# adc-ldo.net
KiCad netlist of a schematic drawn in Altium Designer
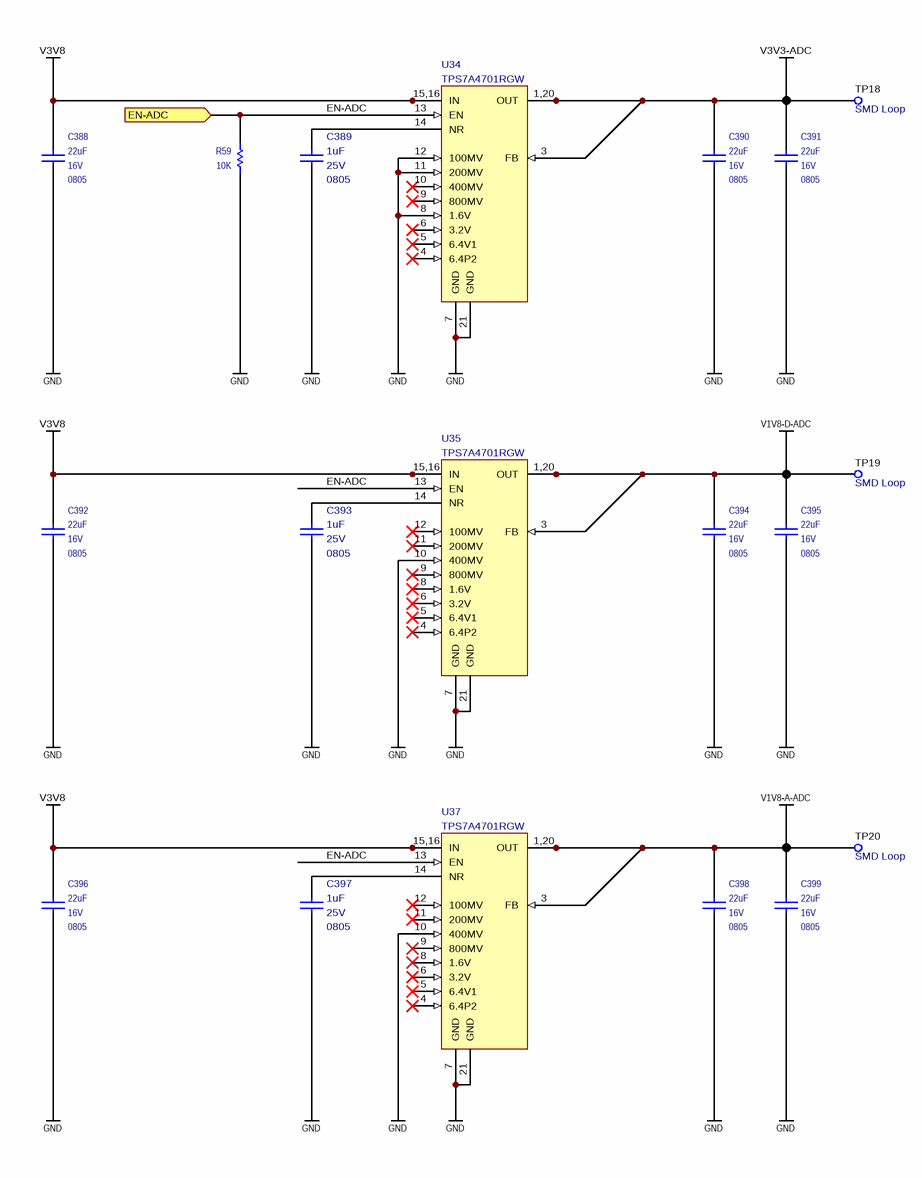
[diagram p0: adc-ldo.SchDoc]

(export (version "E")
  (design (tool "Eeschema 10.0.6"))
  (components
    (comp (ref "C388")
      (value "22uF")
      (footprint "generic:CAPC200X125X145L45N")
      (description "Ceramic Capacitor 22uF ±10% 16V X5R 0805")
      (fields
        (field (name "MANUFACTURER") "Samsung")
        (field (name "VOLTAGE") "16V")
        (field (name "PACKAGE") "0805")
        (field (name "TOLERANCE") "±10%")
      )
      (libsource (lib "generic") (part "CAP 0603"))
    )
    (comp (ref "C389")
      (value "1uF")
      (footprint "CAPC200X125X145L45N")
      (description "Ceramic Capacitor 1uF ±10% 25V X7R 0805")
      (fields
        (field (name "MANUFACTURER") "Taiyo Yuden")
        (field (name "TOLERANCE") "±10%")
        (field (name "PACKAGE") "0805")
        (field (name "VOLTAGE") "25V")
      )
      (libsource (lib "capacitors") (part "CAP"))
    )
    (comp (ref "C390")
      (value "22uF")
      (footprint "generic:CAPC200X125X145L45N")
      (description "Ceramic Capacitor 22uF ±10% 16V X5R 0805")
      (fields
        (field (name "MANUFACTURER") "Samsung")
        (field (name "VOLTAGE") "16V")
        (field (name "PACKAGE") "0805")
        (field (name "TOLERANCE") "±10%")
      )
      (libsource (lib "generic") (part "CAP 0603"))
    )
    (comp (ref "C391")
      (value "22uF")
      (footprint "generic:CAPC200X125X145L45N")
      (description "Ceramic Capacitor 22uF ±10% 16V X5R 0805")
      (fields
        (field (name "MANUFACTURER") "Samsung")
        (field (name "VOLTAGE") "16V")
        (field (name "PACKAGE") "0805")
        (field (name "TOLERANCE") "±10%")
      )
      (libsource (lib "generic") (part "CAP 0603"))
    )
    (comp (ref "C392")
      (value "22uF")
      (footprint "generic:CAPC200X125X145L45N")
      (description "Ceramic Capacitor 22uF ±10% 16V X5R 0805")
      (fields
        (field (name "MANUFACTURER") "Samsung")
        (field (name "VOLTAGE") "16V")
        (field (name "PACKAGE") "0805")
        (field (name "TOLERANCE") "±10%")
      )
      (libsource (lib "generic") (part "CAP 0603"))
    )
    (comp (ref "C393")
      (value "1uF")
      (footprint "CAPC200X125X145L45N")
      (description "Ceramic Capacitor 1uF ±10% 25V X7R 0805")
      (fields
        (field (name "MANUFACTURER") "Taiyo Yuden")
        (field (name "TOLERANCE") "±10%")
        (field (name "PACKAGE") "0805")
        (field (name "VOLTAGE") "25V")
      )
      (libsource (lib "capacitors") (part "CAP"))
    )
    (comp (ref "C394")
      (value "22uF")
      (footprint "generic:CAPC200X125X145L45N")
      (description "Ceramic Capacitor 22uF ±10% 16V X5R 0805")
      (fields
        (field (name "MANUFACTURER") "Samsung")
        (field (name "VOLTAGE") "16V")
        (field (name "PACKAGE") "0805")
        (field (name "TOLERANCE") "±10%")
      )
      (libsource (lib "generic") (part "CAP 0603"))
    )
    (comp (ref "C395")
      (value "22uF")
      (footprint "generic:CAPC200X125X145L45N")
      (description "Ceramic Capacitor 22uF ±10% 16V X5R 0805")
      (fields
        (field (name "MANUFACTURER") "Samsung")
        (field (name "VOLTAGE") "16V")
        (field (name "PACKAGE") "0805")
        (field (name "TOLERANCE") "±10%")
      )
      (libsource (lib "generic") (part "CAP 0603"))
    )
    (comp (ref "C396")
      (value "22uF")
      (footprint "generic:CAPC200X125X145L45N")
      (description "Ceramic Capacitor 22uF ±10% 16V X5R 0805")
      (fields
        (field (name "MANUFACTURER") "Samsung")
        (field (name "VOLTAGE") "16V")
        (field (name "PACKAGE") "0805")
        (field (name "TOLERANCE") "±10%")
      )
      (libsource (lib "generic") (part "CAP 0603"))
    )
    (comp (ref "C397")
      (value "1uF")
      (footprint "CAPC200X125X145L45N")
      (description "Ceramic Capacitor 1uF ±10% 25V X7R 0805")
      (fields
        (field (name "MANUFACTURER") "Taiyo Yuden")
        (field (name "TOLERANCE") "±10%")
        (field (name "PACKAGE") "0805")
        (field (name "VOLTAGE") "25V")
      )
      (libsource (lib "capacitors") (part "CAP"))
    )
    (comp (ref "C398")
      (value "22uF")
      (footprint "generic:CAPC200X125X145L45N")
      (description "Ceramic Capacitor 22uF ±10% 16V X5R 0805")
      (fields
        (field (name "MANUFACTURER") "Samsung")
        (field (name "VOLTAGE") "16V")
        (field (name "PACKAGE") "0805")
        (field (name "TOLERANCE") "±10%")
      )
      (libsource (lib "generic") (part "CAP 0603"))
    )
    (comp (ref "C399")
      (value "22uF")
      (footprint "generic:CAPC200X125X145L45N")
      (description "Ceramic Capacitor 22uF ±10% 16V X5R 0805")
      (fields
        (field (name "MANUFACTURER") "Samsung")
        (field (name "VOLTAGE") "16V")
        (field (name "PACKAGE") "0805")
        (field (name "TOLERANCE") "±10%")
      )
      (libsource (lib "generic") (part "CAP 0603"))
    )
    (comp (ref "R59")
      (value "10K")
      (footprint "RESC1005X40N")
      (description "Thick Film Resistor 10k ±1% 0.1W 50V 0402")
      (fields (field (name "MANUFACTURER") "Panasonic") (field (name "TOLERANCE") "±1%"))
      (libsource (lib "Graviton") (part "RES 0402"))
    )
    (comp (ref "TP18")
      (value "5015")
      (footprint "keystone:5015")
      (description "Test Point SMD")
      (fields (field (name "MANUFACTURER") "Keystone") (field (name "NOTES") "SMD Loop"))
      (libsource (lib "generic") (part "TEST_POINT_SMD_50"))
    )
    (comp (ref "TP19")
      (value "5015")
      (footprint "keystone:5015")
      (description "Test Point SMD")
      (fields (field (name "MANUFACTURER") "Keystone") (field (name "NOTES") "SMD Loop"))
      (libsource (lib "generic") (part "TEST_POINT_SMD_50"))
    )
    (comp (ref "TP20")
      (value "5015")
      (footprint "keystone:5015")
      (description "Test Point SMD")
      (fields (field (name "MANUFACTURER") "Keystone") (field (name "NOTES") "SMD Loop"))
      (libsource (lib "generic") (part "TEST_POINT_SMD_50"))
    )
    (comp (ref "U34")
      (value "TPS7A4701RGW")
      (footprint "QFN65P500X500X100-21N")
      (description "Low-Dropout Linear Regulator 20-VQFN")
      (fields (field (name "MANUFACTURER") "Texas Instruments"))
      (libsource (lib "ti") (part "TPS7A4701RGW_1"))
    )
    (comp (ref "U35")
      (value "TPS7A4701RGW")
      (footprint "QFN65P500X500X100-21N")
      (description "Low-Dropout Linear Regulator 20-VQFN")
      (fields (field (name "MANUFACTURER") "Texas Instruments"))
      (libsource (lib "ti") (part "TPS7A4701RGW_1"))
    )
    (comp (ref "U37")
      (value "TPS7A4701RGW")
      (footprint "QFN65P500X500X100-21N")
      (description "Low-Dropout Linear Regulator 20-VQFN")
      (fields (field (name "MANUFACTURER") "Texas Instruments"))
      (libsource (lib "ti") (part "TPS7A4701RGW_1"))
    )
  )
  (nets
    (net (code "1") (name "/EN-ADC") (class "Default")
      (node (ref "R59") (pin "1") (pinfunction "1_1") (pintype "passive"))
      (node (ref "U34") (pin "13") (pinfunction "EN_13") (pintype "input"))
      (node (ref "U35") (pin "13") (pinfunction "EN_13") (pintype "input"))
      (node (ref "U37") (pin "13") (pinfunction "EN_13") (pintype "input"))
    )
    (net (code "2") (name "GND") (class "Default")
      (node (ref "C388") (pin "1") (pinfunction "1_1") (pintype "passive"))
      (node (ref "C389") (pin "2") (pinfunction "2_2") (pintype "passive"))
      (node (ref "C390") (pin "1") (pinfunction "1_1") (pintype "passive"))
      (node (ref "C391") (pin "1") (pinfunction "1_1") (pintype "passive"))
      (node (ref "C392") (pin "1") (pinfunction "1_1") (pintype "passive"))
      (node (ref "C393") (pin "2") (pinfunction "2_2") (pintype "passive"))
      (node (ref "C394") (pin "1") (pinfunction "1_1") (pintype "passive"))
      (node (ref "C395") (pin "1") (pinfunction "1_1") (pintype "passive"))
      (node (ref "C396") (pin "1") (pinfunction "1_1") (pintype "passive"))
      (node (ref "C397") (pin "2") (pinfunction "2_2") (pintype "passive"))
      (node (ref "C398") (pin "1") (pinfunction "1_1") (pintype "passive"))
      (node (ref "C399") (pin "1") (pinfunction "1_1") (pintype "passive"))
      (node (ref "R59") (pin "2") (pinfunction "2_2") (pintype "passive"))
      (node (ref "U34") (pin "11") (pinfunction "200MV_11") (pintype "input"))
      (node (ref "U34") (pin "12") (pinfunction "100MV_12") (pintype "input"))
      (node (ref "U34") (pin "21") (pinfunction "GND_21") (pintype "power_in"))
      (node (ref "U34") (pin "7") (pinfunction "GND_7") (pintype "power_in"))
      (node (ref "U34") (pin "8") (pinfunction "1.6V_8") (pintype "input"))
      (node (ref "U35") (pin "10") (pinfunction "400MV_10") (pintype "input"))
      (node (ref "U35") (pin "21") (pinfunction "GND_21") (pintype "power_in"))
      (node (ref "U35") (pin "7") (pinfunction "GND_7") (pintype "power_in"))
      (node (ref "U37") (pin "10") (pinfunction "400MV_10") (pintype "input"))
      (node (ref "U37") (pin "21") (pinfunction "GND_21") (pintype "power_in"))
      (node (ref "U37") (pin "7") (pinfunction "GND_7") (pintype "power_in"))
    )
    (net (code "3") (name "Net-(U34-NR)") (class "Default")
      (node (ref "C389") (pin "1") (pinfunction "1_1") (pintype "passive"))
      (node (ref "U34") (pin "14") (pinfunction "NR_14") (pintype "passive"))
    )
    (net (code "4") (name "Net-(U35-NR)") (class "Default")
      (node (ref "C393") (pin "1") (pinfunction "1_1") (pintype "passive"))
      (node (ref "U35") (pin "14") (pinfunction "NR_14") (pintype "passive"))
    )
    (net (code "5") (name "Net-(U37-NR)") (class "Default")
      (node (ref "C397") (pin "1") (pinfunction "1_1") (pintype "passive"))
      (node (ref "U37") (pin "14") (pinfunction "NR_14") (pintype "passive"))
    )
    (net (code "6") (name "V1V8-A-ADC") (class "Default")
      (node (ref "C398") (pin "2") (pinfunction "2_2") (pintype "passive"))
      (node (ref "C399") (pin "2") (pinfunction "2_2") (pintype "passive"))
      (node (ref "TP20") (pin "1") (pinfunction "1_1") (pintype "passive"))
      (node (ref "U37") (pin "1") (pinfunction "OUT_1") (pintype "passive"))
      (node (ref "U37") (pin "20") (pinfunction "OUT_20") (pintype "passive"))
      (node (ref "U37") (pin "3") (pinfunction "FB_3") (pintype "input"))
    )
    (net (code "7") (name "V1V8-D-ADC") (class "Default")
      (node (ref "C394") (pin "2") (pinfunction "2_2") (pintype "passive"))
      (node (ref "C395") (pin "2") (pinfunction "2_2") (pintype "passive"))
      (node (ref "TP19") (pin "1") (pinfunction "1_1") (pintype "passive"))
      (node (ref "U35") (pin "1") (pinfunction "OUT_1") (pintype "passive"))
      (node (ref "U35") (pin "20") (pinfunction "OUT_20") (pintype "passive"))
      (node (ref "U35") (pin "3") (pinfunction "FB_3") (pintype "input"))
    )
    (net (code "8") (name "V3V3-ADC") (class "Default")
      (node (ref "C390") (pin "2") (pinfunction "2_2") (pintype "passive"))
      (node (ref "C391") (pin "2") (pinfunction "2_2") (pintype "passive"))
      (node (ref "TP18") (pin "1") (pinfunction "1_1") (pintype "passive"))
      (node (ref "U34") (pin "1") (pinfunction "OUT_1") (pintype "passive"))
      (node (ref "U34") (pin "20") (pinfunction "OUT_20") (pintype "passive"))
      (node (ref "U34") (pin "3") (pinfunction "FB_3") (pintype "input"))
    )
    (net (code "9") (name "V3V8") (class "Default")
      (node (ref "C388") (pin "2") (pinfunction "2_2") (pintype "passive"))
      (node (ref "C392") (pin "2") (pinfunction "2_2") (pintype "passive"))
      (node (ref "C396") (pin "2") (pinfunction "2_2") (pintype "passive"))
      (node (ref "U34") (pin "15") (pinfunction "IN_15") (pintype "passive"))
      (node (ref "U34") (pin "16") (pinfunction "IN_16") (pintype "passive"))
      (node (ref "U35") (pin "15") (pinfunction "IN_15") (pintype "passive"))
      (node (ref "U35") (pin "16") (pinfunction "IN_16") (pintype "passive"))
      (node (ref "U37") (pin "15") (pinfunction "IN_15") (pintype "passive"))
      (node (ref "U37") (pin "16") (pinfunction "IN_16") (pintype "passive"))
    )
    (net (code "10") (name "unconnected-(U34-3.2V-Pad6)") (class "Default")
      (node (ref "U34") (pin "6") (pinfunction "3.2V_6") (pintype "input+no_connect"))
    )
    (net (code "11") (name "unconnected-(U34-6.4P2-Pad4)") (class "Default")
      (node (ref "U34") (pin "4") (pinfunction "6.4P2_4") (pintype "input+no_connect"))
    )
    (net (code "12") (name "unconnected-(U34-6.4V1-Pad5)") (class "Default")
      (node (ref "U34") (pin "5") (pinfunction "6.4V1_5") (pintype "input+no_connect"))
    )
    (net (code "13") (name "unconnected-(U34-400MV-Pad10)") (class "Default")
      (node (ref "U34") (pin "10") (pinfunction "400MV_10") (pintype "input+no_connect"))
    )
    (net (code "14") (name "unconnected-(U34-800MV-Pad9)") (class "Default")
      (node (ref "U34") (pin "9") (pinfunction "800MV_9") (pintype "input+no_connect"))
    )
    (net (code "15") (name "unconnected-(U35-1.6V-Pad8)") (class "Default")
      (node (ref "U35") (pin "8") (pinfunction "1.6V_8") (pintype "input+no_connect"))
    )
    (net (code "16") (name "unconnected-(U35-3.2V-Pad6)") (class "Default")
      (node (ref "U35") (pin "6") (pinfunction "3.2V_6") (pintype "input+no_connect"))
    )
    (net (code "17") (name "unconnected-(U35-6.4P2-Pad4)") (class "Default")
      (node (ref "U35") (pin "4") (pinfunction "6.4P2_4") (pintype "input+no_connect"))
    )
    (net (code "18") (name "unconnected-(U35-6.4V1-Pad5)") (class "Default")
      (node (ref "U35") (pin "5") (pinfunction "6.4V1_5") (pintype "input+no_connect"))
    )
    (net (code "19") (name "unconnected-(U35-100MV-Pad12)") (class "Default")
      (node (ref "U35") (pin "12") (pinfunction "100MV_12") (pintype "input+no_connect"))
    )
    (net (code "20") (name "unconnected-(U35-200MV-Pad11)") (class "Default")
      (node (ref "U35") (pin "11") (pinfunction "200MV_11") (pintype "input+no_connect"))
    )
    (net (code "21") (name "unconnected-(U35-800MV-Pad9)") (class "Default")
      (node (ref "U35") (pin "9") (pinfunction "800MV_9") (pintype "input+no_connect"))
    )
    (net (code "22") (name "unconnected-(U37-1.6V-Pad8)") (class "Default")
      (node (ref "U37") (pin "8") (pinfunction "1.6V_8") (pintype "input+no_connect"))
    )
    (net (code "23") (name "unconnected-(U37-3.2V-Pad6)") (class "Default")
      (node (ref "U37") (pin "6") (pinfunction "3.2V_6") (pintype "input+no_connect"))
    )
    (net (code "24") (name "unconnected-(U37-6.4P2-Pad4)") (class "Default")
      (node (ref "U37") (pin "4") (pinfunction "6.4P2_4") (pintype "input+no_connect"))
    )
    (net (code "25") (name "unconnected-(U37-6.4V1-Pad5)") (class "Default")
      (node (ref "U37") (pin "5") (pinfunction "6.4V1_5") (pintype "input+no_connect"))
    )
    (net (code "26") (name "unconnected-(U37-100MV-Pad12)") (class "Default")
      (node (ref "U37") (pin "12") (pinfunction "100MV_12") (pintype "input+no_connect"))
    )
    (net (code "27") (name "unconnected-(U37-200MV-Pad11)") (class "Default")
      (node (ref "U37") (pin "11") (pinfunction "200MV_11") (pintype "input+no_connect"))
    )
    (net (code "28") (name "unconnected-(U37-800MV-Pad9)") (class "Default")
      (node (ref "U37") (pin "9") (pinfunction "800MV_9") (pintype "input+no_connect"))
    )
  )
)
